# 3_TopLevel.net
KiCad netlist of a schematic drawn in Altium Designer
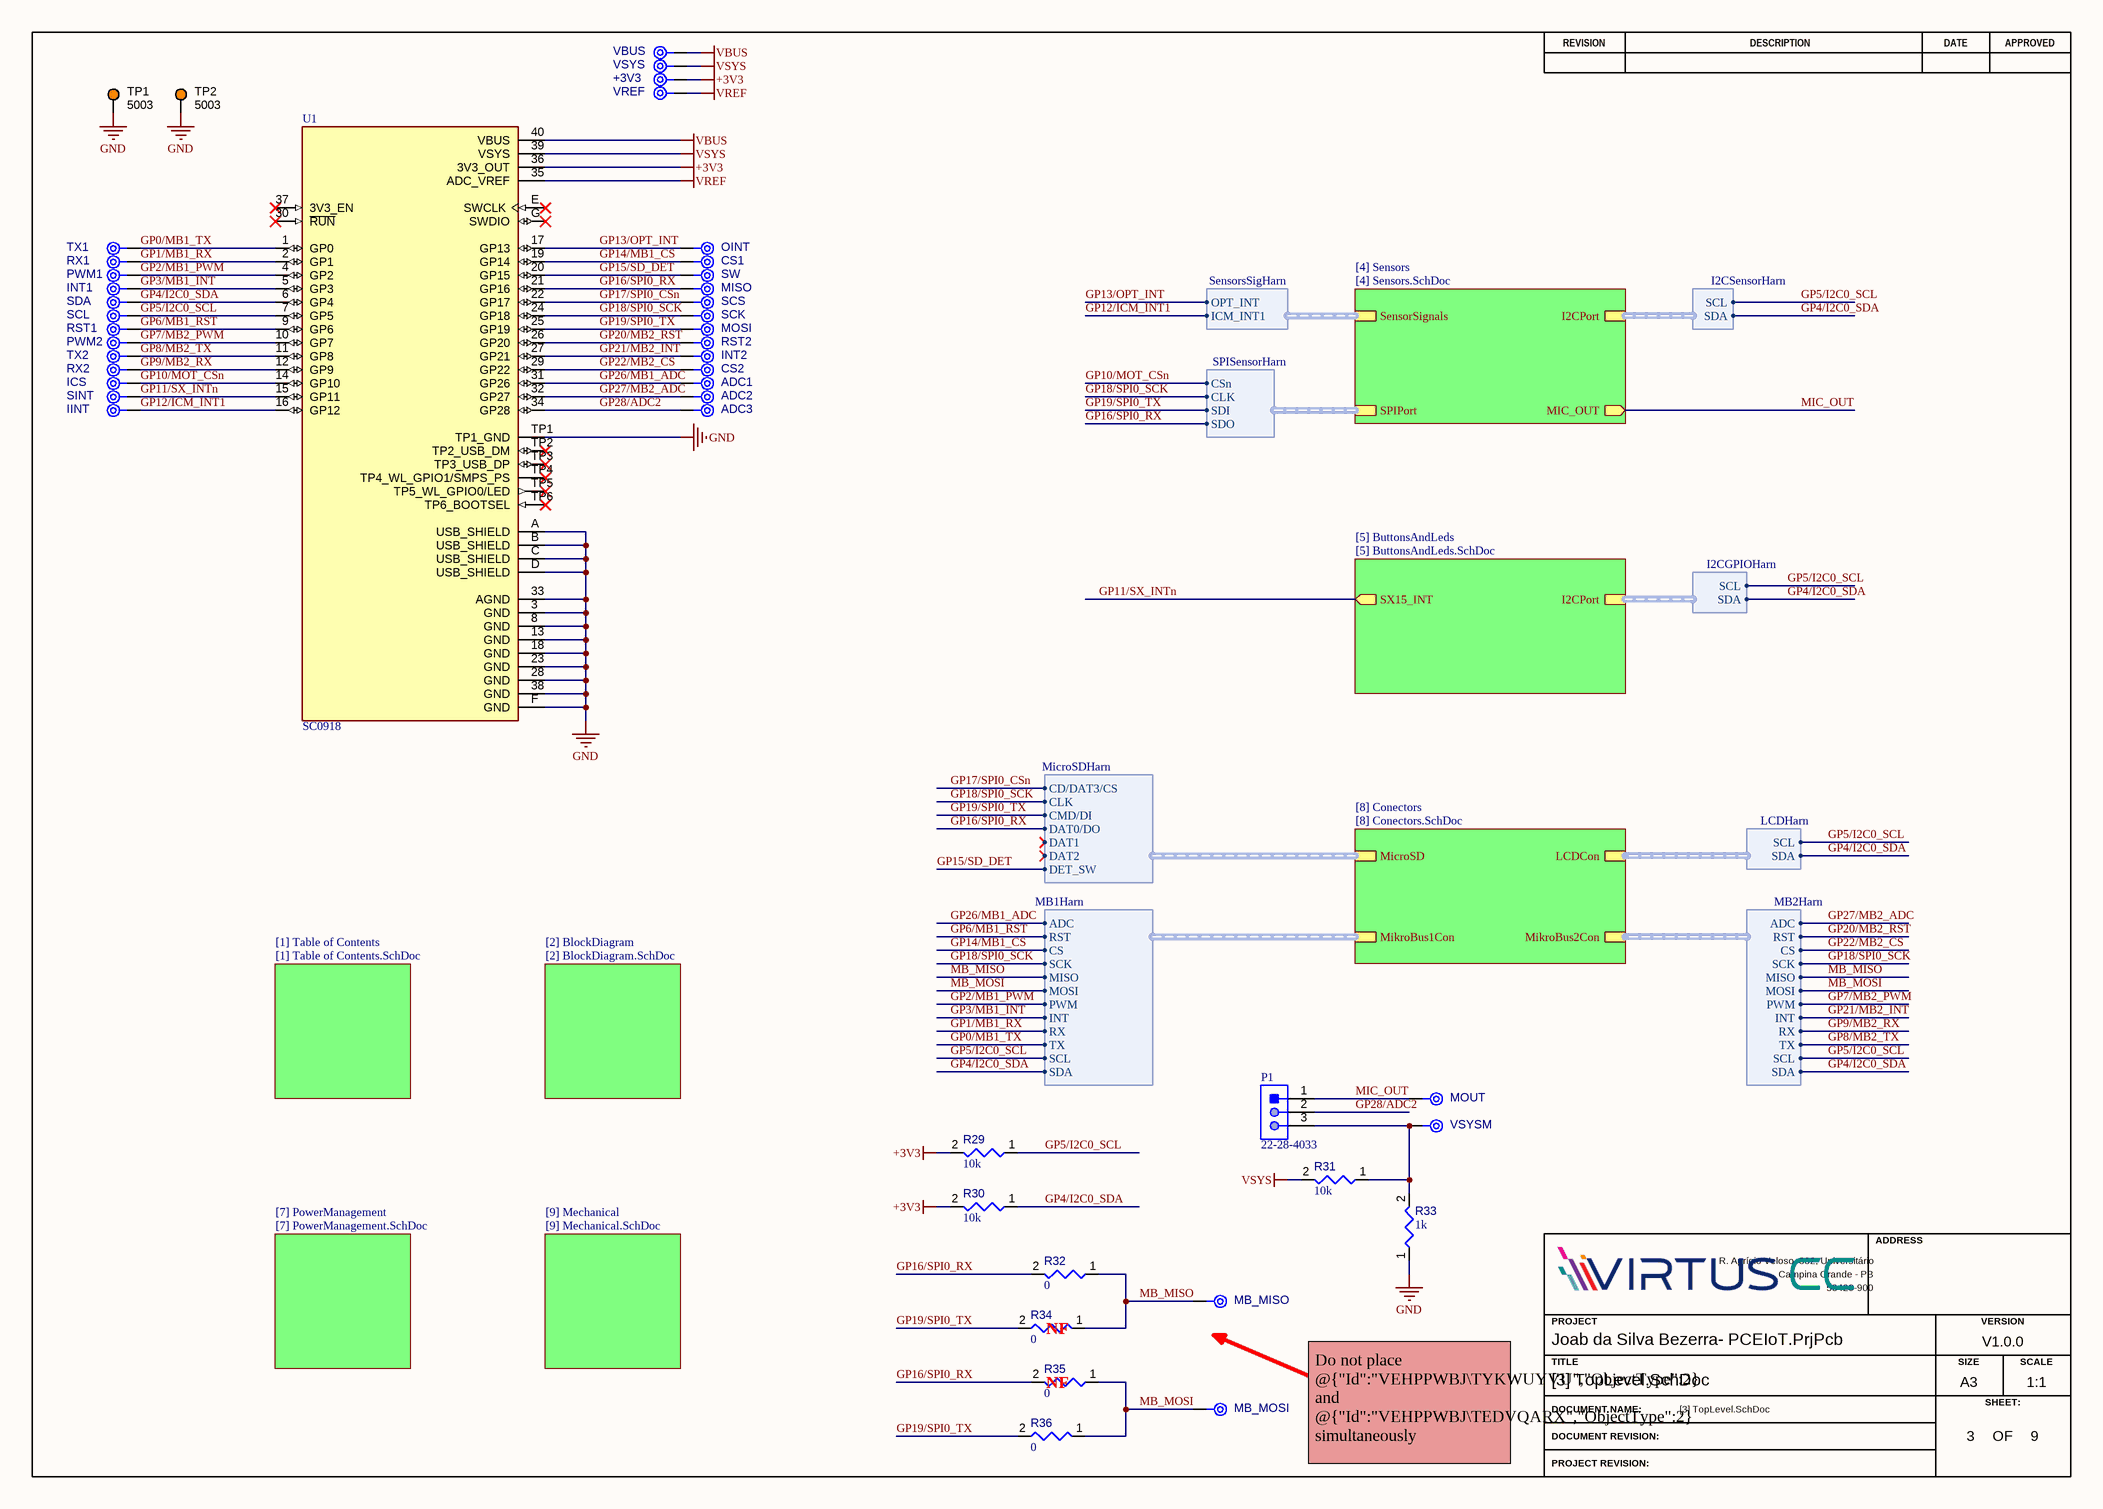
[diagram p0: [3] TopLevel.SchDoc]

(export (version "E")
  (design (tool "Eeschema 10.0.6"))
  (components
    (comp (ref "+3V3")
      (value "TPAD6R")
      (footprint "TP06R")
      (description "0.6mm round")
      (libsource (lib "UFCG - Universidade Federal de Campina Grande") (part "CMP-001-0001-4"))
    )
    (comp (ref "ADC1")
      (value "TPAD6R")
      (footprint "TP06R")
      (description "0.6mm round")
      (libsource (lib "UFCG - Universidade Federal de Campina Grande") (part "CMP-001-0001-4"))
    )
    (comp (ref "ADC2")
      (value "TPAD6R")
      (footprint "TP06R")
      (description "0.6mm round")
      (libsource (lib "UFCG - Universidade Federal de Campina Grande") (part "CMP-001-0001-4"))
    )
    (comp (ref "ADC3")
      (value "TPAD6R")
      (footprint "TP06R")
      (description "0.6mm round")
      (libsource (lib "UFCG - Universidade Federal de Campina Grande") (part "CMP-001-0001-4"))
    )
    (comp (ref "CS1")
      (value "TPAD6R")
      (footprint "TP06R")
      (description "0.6mm round")
      (libsource (lib "UFCG - Universidade Federal de Campina Grande") (part "CMP-001-0001-4"))
    )
    (comp (ref "CS2")
      (value "TPAD6R")
      (footprint "TP06R")
      (description "0.6mm round")
      (libsource (lib "UFCG - Universidade Federal de Campina Grande") (part "CMP-001-0001-4"))
    )
    (comp (ref "ICS")
      (value "TPAD6R")
      (footprint "TP06R")
      (description "0.6mm round")
      (libsource (lib "UFCG - Universidade Federal de Campina Grande") (part "CMP-001-0001-4"))
    )
    (comp (ref "IINT")
      (value "TPAD6R")
      (footprint "TP06R")
      (description "0.6mm round")
      (libsource (lib "UFCG - Universidade Federal de Campina Grande") (part "CMP-001-0001-4"))
    )
    (comp (ref "INT1")
      (value "TPAD6R")
      (footprint "TP06R")
      (description "0.6mm round")
      (libsource (lib "UFCG - Universidade Federal de Campina Grande") (part "CMP-001-0001-4"))
    )
    (comp (ref "INT2")
      (value "TPAD6R")
      (footprint "TP06R")
      (description "0.6mm round")
      (libsource (lib "UFCG - Universidade Federal de Campina Grande") (part "CMP-001-0001-4"))
    )
    (comp (ref "MB_MISO")
      (value "TPAD6R")
      (footprint "TP06R")
      (description "0.6mm round")
      (libsource (lib "UFCG - Universidade Federal de Campina Grande") (part "CMP-001-0001-4"))
    )
    (comp (ref "MB_MOSI")
      (value "TPAD6R")
      (footprint "TP06R")
      (description "0.6mm round")
      (libsource (lib "UFCG - Universidade Federal de Campina Grande") (part "CMP-001-0001-4"))
    )
    (comp (ref "MISO")
      (value "TPAD6R")
      (footprint "TP06R")
      (description "0.6mm round")
      (libsource (lib "UFCG - Universidade Federal de Campina Grande") (part "CMP-001-0001-4"))
    )
    (comp (ref "MOSI")
      (value "TPAD6R")
      (footprint "TP06R")
      (description "0.6mm round")
      (libsource (lib "UFCG - Universidade Federal de Campina Grande") (part "CMP-001-0001-4"))
    )
    (comp (ref "MOUT")
      (value "TPAD6R")
      (footprint "TP06R")
      (description "0.6mm round")
      (libsource (lib "UFCG - Universidade Federal de Campina Grande") (part "CMP-001-0001-4"))
    )
    (comp (ref "OINT")
      (value "TPAD6R")
      (footprint "TP06R")
      (description "0.6mm round")
      (libsource (lib "UFCG - Universidade Federal de Campina Grande") (part "CMP-001-0001-4"))
    )
    (comp (ref "P1")
      (value "22-28-4033")
      (footprint "MOLX-22-28-4033_V")
      (description "KK 254 Breakaway Header Vertical 3 Circuits 0.38um Gold Selective Plating Mating Pin 6.09mm")
      (libsource (lib "UFCG - Universidade Federal de Campina Grande") (part "CN-1P-M-R3"))
    )
    (comp (ref "PWM1")
      (value "TPAD6R")
      (footprint "TP06R")
      (description "0.6mm round")
      (libsource (lib "UFCG - Universidade Federal de Campina Grande") (part "CMP-001-0001-4"))
    )
    (comp (ref "PWM2")
      (value "TPAD6R")
      (footprint "TP06R")
      (description "0.6mm round")
      (libsource (lib "UFCG - Universidade Federal de Campina Grande") (part "CMP-001-0001-4"))
    )
    (comp (ref "R29")
      (value "10k")
      (footprint "RESC0603(1608)_L")
      (description "Chip Resistor, 10 KOhm, +/- 1%, 01 W, -55 to 155 degC, 0603 (1608 Metric)")
      (fields (field (name "POWER") "100mW") (field (name "TOLERANCE") "1%"))
      (libsource (lib "UFCG - Universidade Federal de Campina Grande") (part "RES-2"))
    )
    (comp (ref "R30")
      (value "10k")
      (footprint "RESC0603(1608)_L")
      (description "Chip Resistor, 10 KOhm, +/- 1%, 01 W, -55 to 155 degC, 0603 (1608 Metric)")
      (fields (field (name "POWER") "100mW") (field (name "TOLERANCE") "1%"))
      (libsource (lib "UFCG - Universidade Federal de Campina Grande") (part "RES-2"))
    )
    (comp (ref "R31")
      (value "10k")
      (footprint "RESC0603(1608)_L")
      (description "Chip Resistor, 10 KOhm, +/- 1%, 01 W, -55 to 155 degC, 0603 (1608 Metric)")
      (fields (field (name "POWER") "100mW") (field (name "TOLERANCE") "1%"))
      (libsource (lib "UFCG - Universidade Federal de Campina Grande") (part "RES-2"))
    )
    (comp (ref "R32")
      (value "0")
      (footprint "RESC0603(1608)_L")
      (description "Chip Resistor, 0 Ohm, 0.1 W, -55 to 155 degC, 0603 (1608 Metric)")
      (fields (field (name "TOLERANCE") "5%") (field (name "POWER") "100mW"))
      (libsource (lib "UFCG - Universidade Federal de Campina Grande") (part "RES-2"))
    )
    (comp (ref "R33")
      (value "1k")
      (footprint "RESC0603(1608)_L")
      (description "Chip Resistor, 1 KOhm, +/-1%, 0.1 W, -55 to 155 degC, 0603 (1608 Metric)")
      (fields (field (name "POWER") "100mW") (field (name "TOLERANCE") "1%"))
      (libsource (lib "UFCG - Universidade Federal de Campina Grande") (part "RES-2"))
    )
    (comp (ref "R34")
      (value "0")
      (footprint "RESC0603(1608)_L")
      (description "Chip Resistor, 0 Ohm, 0.1 W, -55 to 155 degC, 0603 (1608 Metric)")
      (fields (field (name "TOLERANCE") "5%") (field (name "POWER") "100mW"))
      (libsource (lib "UFCG - Universidade Federal de Campina Grande") (part "RES-2"))
    )
    (comp (ref "R35")
      (value "0")
      (footprint "RESC0603(1608)_L")
      (description "Chip Resistor, 0 Ohm, 0.1 W, -55 to 155 degC, 0603 (1608 Metric)")
      (fields (field (name "TOLERANCE") "5%") (field (name "POWER") "100mW"))
      (libsource (lib "UFCG - Universidade Federal de Campina Grande") (part "RES-2"))
    )
    (comp (ref "R36")
      (value "0")
      (footprint "RESC0603(1608)_L")
      (description "Chip Resistor, 0 Ohm, 0.1 W, -55 to 155 degC, 0603 (1608 Metric)")
      (fields (field (name "TOLERANCE") "5%") (field (name "POWER") "100mW"))
      (libsource (lib "UFCG - Universidade Federal de Campina Grande") (part "RES-2"))
    )
    (comp (ref "RST1")
      (value "TPAD6R")
      (footprint "TP06R")
      (description "0.6mm round")
      (libsource (lib "UFCG - Universidade Federal de Campina Grande") (part "CMP-001-0001-4"))
    )
    (comp (ref "RST2")
      (value "TPAD6R")
      (footprint "TP06R")
      (description "0.6mm round")
      (libsource (lib "UFCG - Universidade Federal de Campina Grande") (part "CMP-001-0001-4"))
    )
    (comp (ref "RX1")
      (value "TPAD6R")
      (footprint "TP06R")
      (description "0.6mm round")
      (libsource (lib "UFCG - Universidade Federal de Campina Grande") (part "CMP-001-0001-4"))
    )
    (comp (ref "RX2")
      (value "TPAD6R")
      (footprint "TP06R")
      (description "0.6mm round")
      (libsource (lib "UFCG - Universidade Federal de Campina Grande") (part "CMP-001-0001-4"))
    )
    (comp (ref "SCK")
      (value "TPAD6R")
      (footprint "TP06R")
      (description "0.6mm round")
      (libsource (lib "UFCG - Universidade Federal de Campina Grande") (part "CMP-001-0001-4"))
    )
    (comp (ref "SCL")
      (value "TPAD6R")
      (footprint "TP06R")
      (description "0.6mm round")
      (libsource (lib "UFCG - Universidade Federal de Campina Grande") (part "CMP-001-0001-4"))
    )
    (comp (ref "SCS")
      (value "TPAD6R")
      (footprint "TP06R")
      (description "0.6mm round")
      (libsource (lib "UFCG - Universidade Federal de Campina Grande") (part "CMP-001-0001-4"))
    )
    (comp (ref "SDA")
      (value "TPAD6R")
      (footprint "TP06R")
      (description "0.6mm round")
      (libsource (lib "UFCG - Universidade Federal de Campina Grande") (part "CMP-001-0001-4"))
    )
    (comp (ref "SINT")
      (value "TPAD6R")
      (footprint "TP06R")
      (description "0.6mm round")
      (libsource (lib "UFCG - Universidade Federal de Campina Grande") (part "CMP-001-0001-4"))
    )
    (comp (ref "SW")
      (value "TPAD6R")
      (footprint "TP06R")
      (description "0.6mm round")
      (libsource (lib "UFCG - Universidade Federal de Campina Grande") (part "CMP-001-0001-4"))
    )
    (comp (ref "TP1")
      (value "5003")
      (footprint "KSTN-5003")
      (description "Test Point, Orange, Height 4.6 mm, Tail Length 3 mm, 1-Pin THD, RoHS")
      (fields (field (name "MANUFACTURER") "Keystone"))
      (libsource (lib "UFCG - Universidade Federal de Campina Grande") (part "TESTPOINT_ORANGE"))
    )
    (comp (ref "TP2")
      (value "5003")
      (footprint "KSTN-5003")
      (description "Test Point, Orange, Height 4.6 mm, Tail Length 3 mm, 1-Pin THD, RoHS")
      (fields (field (name "MANUFACTURER") "Keystone"))
      (libsource (lib "UFCG - Universidade Federal de Campina Grande") (part "TESTPOINT_ORANGE"))
    )
    (comp (ref "TX1")
      (value "TPAD6R")
      (footprint "TP06R")
      (description "0.6mm round")
      (libsource (lib "UFCG - Universidade Federal de Campina Grande") (part "CMP-001-0001-4"))
    )
    (comp (ref "TX2")
      (value "TPAD6R")
      (footprint "TP06R")
      (description "0.6mm round")
      (libsource (lib "UFCG - Universidade Federal de Campina Grande") (part "CMP-001-0001-4"))
    )
    (comp (ref "U1")
      (value "SC0918")
      (footprint "MODULE_SC0918")
      (description "Raspberry Pi Pico W RP2040")
      (fields (field (name "MF") "Raspberry Pi"))
      (libsource (lib "PCEIOT") (part "CMP-006-000001-6"))
    )
    (comp (ref "VBUS")
      (value "TPAD6R")
      (footprint "TP06R")
      (description "0.6mm round")
      (libsource (lib "UFCG - Universidade Federal de Campina Grande") (part "CMP-001-0001-4"))
    )
    (comp (ref "VREF")
      (value "TPAD6R")
      (footprint "TP06R")
      (description "0.6mm round")
      (libsource (lib "UFCG - Universidade Federal de Campina Grande") (part "CMP-001-0001-4"))
    )
    (comp (ref "VSYS")
      (value "TPAD6R")
      (footprint "TP06R")
      (description "0.6mm round")
      (libsource (lib "UFCG - Universidade Federal de Campina Grande") (part "CMP-001-0001-4"))
    )
    (comp (ref "VSYSM")
      (value "TPAD6R")
      (footprint "TP06R")
      (description "0.6mm round")
      (libsource (lib "UFCG - Universidade Federal de Campina Grande") (part "CMP-001-0001-4"))
    )
  )
  (nets
    (net (code "9") (name "+3V3") (class "Default")
      (node (ref "+3V3") (pin "1") (pinfunction "TP_1") (pintype "passive"))
      (node (ref "R29") (pin "2") (pinfunction "2_2") (pintype "passive"))
      (node (ref "R30") (pin "2") (pinfunction "2_2") (pintype "passive"))
      (node (ref "U1") (pin "36") (pinfunction "3V3_OUT_36") (pintype "power_in"))
    )
    (net (code "10") (name "/GP0{slash}MB1_TX") (class "Default")
      (node (ref "TX1") (pin "1") (pinfunction "TP_1") (pintype "passive"))
      (node (ref "U1") (pin "1") (pinfunction "GP0_1") (pintype "bidirectional"))
    )
    (net (code "11") (name "/GP1{slash}MB1_RX") (class "Default")
      (node (ref "RX1") (pin "1") (pinfunction "TP_1") (pintype "passive"))
      (node (ref "U1") (pin "2") (pinfunction "GP1_2") (pintype "bidirectional"))
    )
    (net (code "12") (name "/GP2{slash}MB1_PWM") (class "Default")
      (node (ref "PWM1") (pin "1") (pinfunction "TP_1") (pintype "passive"))
      (node (ref "U1") (pin "4") (pinfunction "GP2_4") (pintype "bidirectional"))
    )
    (net (code "13") (name "/GP3{slash}MB1_INT") (class "Default")
      (node (ref "INT1") (pin "1") (pinfunction "TP_1") (pintype "passive"))
      (node (ref "U1") (pin "5") (pinfunction "GP3_5") (pintype "bidirectional"))
    )
    (net (code "14") (name "/GP4{slash}I2C0_SDA") (class "Default")
      (node (ref "R30") (pin "1") (pinfunction "1_1") (pintype "passive"))
      (node (ref "SDA") (pin "1") (pinfunction "TP_1") (pintype "passive"))
      (node (ref "U1") (pin "6") (pinfunction "GP4_6") (pintype "bidirectional"))
    )
    (net (code "15") (name "/GP5{slash}I2C0_SCL") (class "Default")
      (node (ref "R29") (pin "1") (pinfunction "1_1") (pintype "passive"))
      (node (ref "SCL") (pin "1") (pinfunction "TP_1") (pintype "passive"))
      (node (ref "U1") (pin "7") (pinfunction "GP5_7") (pintype "bidirectional"))
    )
    (net (code "16") (name "/GP6{slash}MB1_RST") (class "Default")
      (node (ref "RST1") (pin "1") (pinfunction "TP_1") (pintype "passive"))
      (node (ref "U1") (pin "9") (pinfunction "GP6_9") (pintype "bidirectional"))
    )
    (net (code "17") (name "/GP7{slash}MB2_PWM") (class "Default")
      (node (ref "PWM2") (pin "1") (pinfunction "TP_1") (pintype "passive"))
      (node (ref "U1") (pin "10") (pinfunction "GP7_10") (pintype "bidirectional"))
    )
    (net (code "18") (name "/GP8{slash}MB2_TX") (class "Default")
      (node (ref "TX2") (pin "1") (pinfunction "TP_1") (pintype "passive"))
      (node (ref "U1") (pin "11") (pinfunction "GP8_11") (pintype "bidirectional"))
    )
    (net (code "19") (name "/GP9{slash}MB2_RX") (class "Default")
      (node (ref "RX2") (pin "1") (pinfunction "TP_1") (pintype "passive"))
      (node (ref "U1") (pin "12") (pinfunction "GP9_12") (pintype "bidirectional"))
    )
    (net (code "20") (name "/GP10{slash}MOT_CSn") (class "Default")
      (node (ref "ICS") (pin "1") (pinfunction "TP_1") (pintype "passive"))
      (node (ref "U1") (pin "14") (pinfunction "GP10_14") (pintype "bidirectional"))
    )
    (net (code "21") (name "/GP11{slash}SX_INTn") (class "Default")
      (node (ref "SINT") (pin "1") (pinfunction "TP_1") (pintype "passive"))
      (node (ref "U1") (pin "15") (pinfunction "GP11_15") (pintype "bidirectional"))
    )
    (net (code "22") (name "/GP12{slash}ICM_INT1") (class "Default")
      (node (ref "IINT") (pin "1") (pinfunction "TP_1") (pintype "passive"))
      (node (ref "U1") (pin "16") (pinfunction "GP12_16") (pintype "bidirectional"))
    )
    (net (code "23") (name "/GP13{slash}OPT_INT") (class "Default")
      (node (ref "OINT") (pin "1") (pinfunction "TP_1") (pintype "passive"))
      (node (ref "U1") (pin "17") (pinfunction "GP13_17") (pintype "bidirectional"))
    )
    (net (code "24") (name "/GP14{slash}MB1_CS") (class "Default")
      (node (ref "CS1") (pin "1") (pinfunction "TP_1") (pintype "passive"))
      (node (ref "U1") (pin "19") (pinfunction "GP14_19") (pintype "bidirectional"))
    )
    (net (code "25") (name "/GP15{slash}SD_DET") (class "Default")
      (node (ref "SW") (pin "1") (pinfunction "TP_1") (pintype "passive"))
      (node (ref "U1") (pin "20") (pinfunction "GP15_20") (pintype "bidirectional"))
    )
    (net (code "26") (name "/GP16{slash}SPI0_RX") (class "Default")
      (node (ref "MISO") (pin "1") (pinfunction "TP_1") (pintype "passive"))
      (node (ref "R32") (pin "2") (pinfunction "2_2") (pintype "passive"))
      (node (ref "R35") (pin "2") (pinfunction "2_2") (pintype "passive"))
      (node (ref "U1") (pin "21") (pinfunction "GP16_21") (pintype "bidirectional"))
    )
    (net (code "27") (name "/GP17{slash}SPI0_CSn") (class "Default")
      (node (ref "SCS") (pin "1") (pinfunction "TP_1") (pintype "passive"))
      (node (ref "U1") (pin "22") (pinfunction "GP17_22") (pintype "bidirectional"))
    )
    (net (code "28") (name "/GP18{slash}SPI0_SCK") (class "Default")
      (node (ref "SCK") (pin "1") (pinfunction "TP_1") (pintype "passive"))
      (node (ref "U1") (pin "24") (pinfunction "GP18_24") (pintype "bidirectional"))
    )
    (net (code "29") (name "/GP19{slash}SPI0_TX") (class "Default")
      (node (ref "MOSI") (pin "1") (pinfunction "TP_1") (pintype "passive"))
      (node (ref "R34") (pin "2") (pinfunction "2_2") (pintype "passive"))
      (node (ref "R36") (pin "2") (pinfunction "2_2") (pintype "passive"))
      (node (ref "U1") (pin "25") (pinfunction "GP19_25") (pintype "bidirectional"))
    )
    (net (code "30") (name "/GP20{slash}MB2_RST") (class "Default")
      (node (ref "RST2") (pin "1") (pinfunction "TP_1") (pintype "passive"))
      (node (ref "U1") (pin "26") (pinfunction "GP20_26") (pintype "bidirectional"))
    )
    (net (code "31") (name "/GP21{slash}MB2_INT") (class "Default")
      (node (ref "INT2") (pin "1") (pinfunction "TP_1") (pintype "passive"))
      (node (ref "U1") (pin "27") (pinfunction "GP21_27") (pintype "bidirectional"))
    )
    (net (code "32") (name "/GP22{slash}MB2_CS") (class "Default")
      (node (ref "CS2") (pin "1") (pinfunction "TP_1") (pintype "passive"))
      (node (ref "U1") (pin "29") (pinfunction "GP22_29") (pintype "bidirectional"))
    )
    (net (code "33") (name "/GP26{slash}MB1_ADC") (class "Default")
      (node (ref "ADC1") (pin "1") (pinfunction "TP_1") (pintype "passive"))
      (node (ref "U1") (pin "31") (pinfunction "GP26_31") (pintype "bidirectional"))
    )
    (net (code "34") (name "/GP27{slash}MB2_ADC") (class "Default")
      (node (ref "ADC2") (pin "1") (pinfunction "TP_1") (pintype "passive"))
      (node (ref "U1") (pin "32") (pinfunction "GP27_32") (pintype "bidirectional"))
    )
    (net (code "35") (name "/GP28{slash}ADC2") (class "Default")
      (node (ref "ADC3") (pin "1") (pinfunction "TP_1") (pintype "passive"))
      (node (ref "P1") (pin "2") (pinfunction "2_2") (pintype "passive"))
      (node (ref "U1") (pin "34") (pinfunction "GP28_34") (pintype "bidirectional"))
    )
    (net (code "36") (name "/MB_MISO") (class "Default")
      (node (ref "MB_MISO") (pin "1") (pinfunction "TP_1") (pintype "passive"))
      (node (ref "R32") (pin "1") (pinfunction "1_1") (pintype "passive"))
      (node (ref "R34") (pin "1") (pinfunction "1_1") (pintype "passive"))
    )
    (net (code "37") (name "/MB_MOSI") (class "Default")
      (node (ref "MB_MOSI") (pin "1") (pinfunction "TP_1") (pintype "passive"))
      (node (ref "R35") (pin "1") (pinfunction "1_1") (pintype "passive"))
      (node (ref "R36") (pin "1") (pinfunction "1_1") (pintype "passive"))
    )
    (net (code "38") (name "/MIC_OUT") (class "Default")
      (node (ref "MOUT") (pin "1") (pinfunction "TP_1") (pintype "passive"))
      (node (ref "P1") (pin "1") (pinfunction "1_1") (pintype "passive"))
    )
    (net (code "47") (name "GND") (class "Default")
      (node (ref "R33") (pin "1") (pinfunction "1_1") (pintype "passive"))
      (node (ref "TP1") (pin "1") (pinfunction "1_1") (pintype "passive"))
      (node (ref "TP2") (pin "1") (pinfunction "1_1") (pintype "passive"))
      (node (ref "U1") (pin "13") (pinfunction "GND_13") (pintype "power_in"))
      (node (ref "U1") (pin "18") (pinfunction "GND_18") (pintype "power_in"))
      (node (ref "U1") (pin "23") (pinfunction "GND_23") (pintype "power_in"))
      (node (ref "U1") (pin "28") (pinfunction "GND_28") (pintype "power_in"))
      (node (ref "U1") (pin "3") (pinfunction "GND_3") (pintype "power_in"))
      (node (ref "U1") (pin "33") (pinfunction "AGND_33") (pintype "power_in"))
      (node (ref "U1") (pin "38") (pinfunction "GND_38") (pintype "power_in"))
      (node (ref "U1") (pin "8") (pinfunction "GND_8") (pintype "power_in"))
      (node (ref "U1") (pin "A") (pinfunction "USB_SHIELD_A") (pintype "power_in"))
      (node (ref "U1") (pin "B") (pinfunction "USB_SHIELD_B") (pintype "power_in"))
      (node (ref "U1") (pin "C") (pinfunction "USB_SHIELD_C") (pintype "power_in"))
      (node (ref "U1") (pin "D") (pinfunction "USB_SHIELD_D") (pintype "power_in"))
      (node (ref "U1") (pin "F") (pinfunction "GND_F") (pintype "power_in"))
      (node (ref "U1") (pin "TP1") (pinfunction "TP1_GND_TP1") (pintype "power_in"))
    )
    (net (code "48") (name "Net-(VSYSM-TP)") (class "Default")
      (node (ref "P1") (pin "3") (pinfunction "3_3") (pintype "passive"))
      (node (ref "R31") (pin "1") (pinfunction "1_1") (pintype "passive"))
      (node (ref "R33") (pin "2") (pinfunction "2_2") (pintype "passive"))
      (node (ref "VSYSM") (pin "1") (pinfunction "TP_1") (pintype "passive"))
    )
    (net (code "49") (name "VBUS") (class "Default")
      (node (ref "U1") (pin "40") (pinfunction "VBUS_40") (pintype "power_in"))
      (node (ref "VBUS") (pin "1") (pinfunction "TP_1") (pintype "passive"))
    )
    (net (code "50") (name "VREF") (class "Default")
      (node (ref "U1") (pin "35") (pinfunction "ADC_VREF_35") (pintype "power_in"))
      (node (ref "VREF") (pin "1") (pinfunction "TP_1") (pintype "passive"))
    )
    (net (code "51") (name "VSYS") (class "Default")
      (node (ref "R31") (pin "2") (pinfunction "2_2") (pintype "passive"))
      (node (ref "U1") (pin "39") (pinfunction "VSYS_39") (pintype "power_in"))
      (node (ref "VSYS") (pin "1") (pinfunction "TP_1") (pintype "passive"))
    )
    (net (code "52") (name "unconnected-(U1-3V3_EN-Pad37)") (class "Default")
      (node (ref "U1") (pin "37") (pinfunction "3V3_EN_37") (pintype "input+no_connect"))
    )
    (net (code "53") (name "unconnected-(U1-SWCLK-PadE)") (class "Default")
      (node (ref "U1") (pin "E") (pinfunction "SWCLK_E") (pintype "input+no_connect"))
    )
    (net (code "54") (name "unconnected-(U1-SWDIO-PadG)") (class "Default")
      (node (ref "U1") (pin "G") (pinfunction "SWDIO_G") (pintype "bidirectional+no_connect"))
    )
    (net (code "55") (name "unconnected-(U1-TP2_USB_DM-PadTP2)") (class "Default")
      (node (ref "U1") (pin "TP2") (pinfunction "TP2_USB_DM_TP2") (pintype "bidirectional+no_connect"))
    )
    (net (code "56") (name "unconnected-(U1-TP3_USB_DP-PadTP3)") (class "Default")
      (node (ref "U1") (pin "TP3") (pinfunction "TP3_USB_DP_TP3") (pintype "bidirectional+no_connect"))
    )
    (net (code "57") (name "unconnected-(U1-TP4_WL_GPIO1{slash}SMPS_PS-PadTP4)") (class "Default")
      (node (ref "U1") (pin "TP4") (pinfunction "TP4_WL_GPIO1/SMPS_PS_TP4") (pintype "passive+no_connect"))
    )
    (net (code "58") (name "unconnected-(U1-TP5_WL_GPIO0{slash}LED-PadTP5)") (class "Default")
      (node (ref "U1") (pin "TP5") (pinfunction "TP5_WL_GPIO0/LED_TP5") (pintype "output+no_connect"))
    )
    (net (code "59") (name "unconnected-(U1-TP6_BOOTSEL-PadTP6)") (class "Default")
      (node (ref "U1") (pin "TP6") (pinfunction "TP6_BOOTSEL_TP6") (pintype "input+no_connect"))
    )
    (net (code "60") (name "unconnected-(U1-~{RUN}-Pad30)") (class "Default")
      (node (ref "U1") (pin "30") (pinfunction "~{RUN}_30") (pintype "input+no_connect"))
    )
  )
)
